# Sch1.net
KiCad netlist of a schematic drawn in Altium Designer
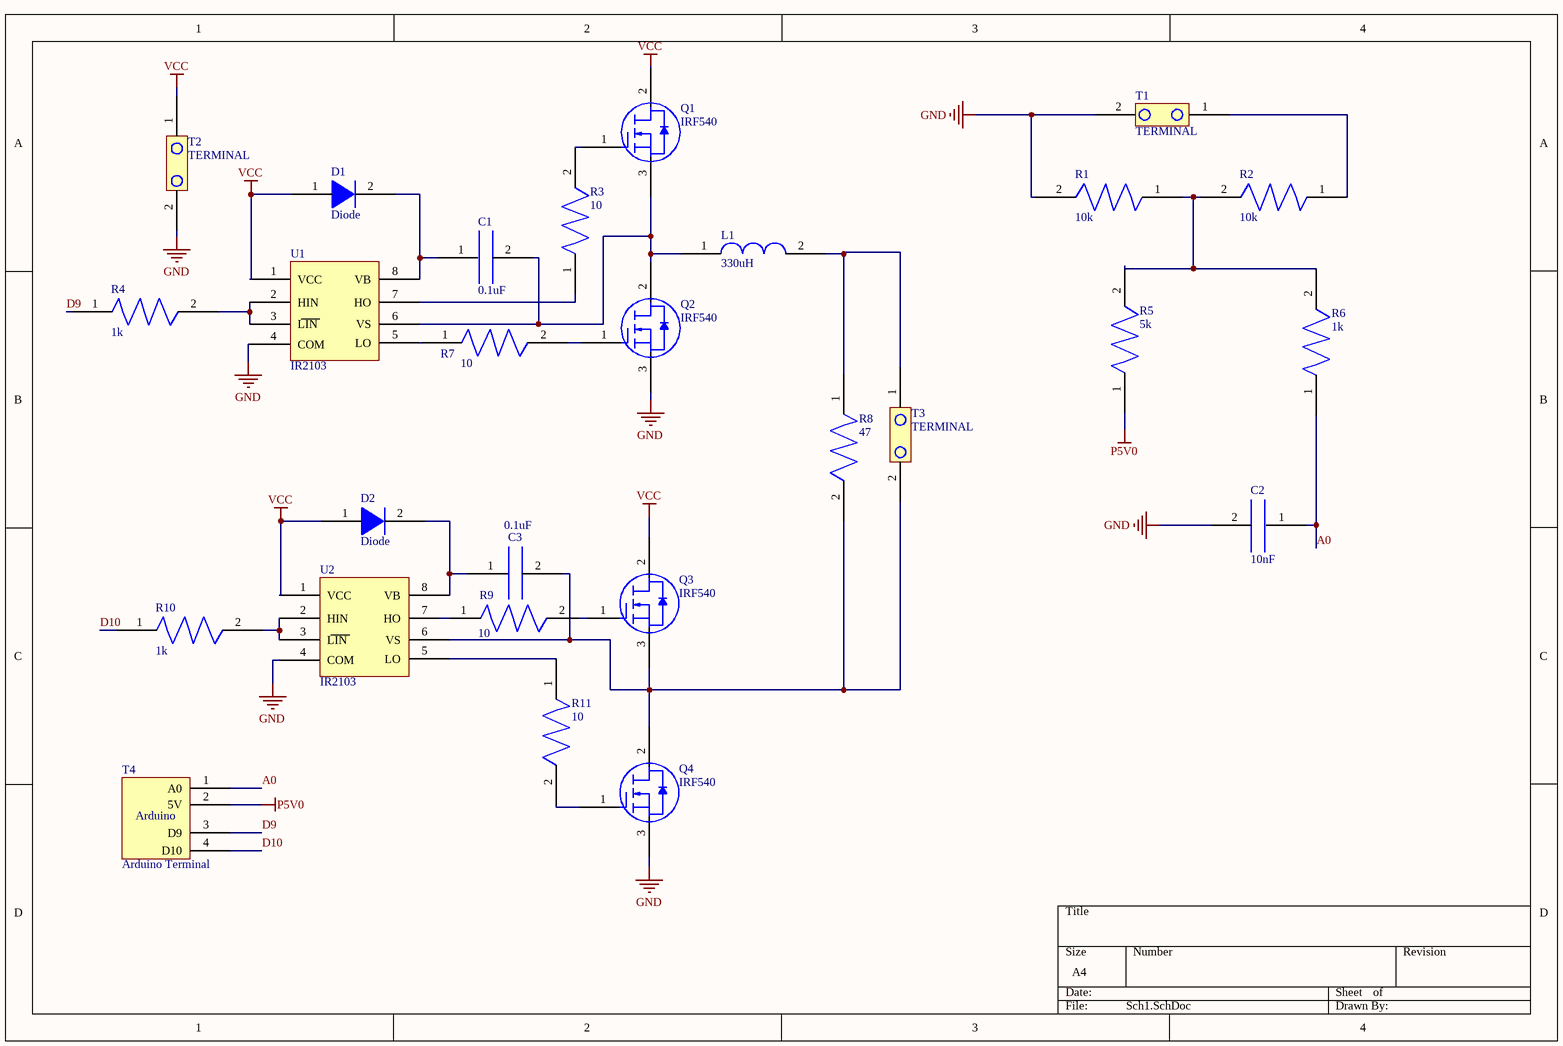
[diagram p0: Sch1.SchDoc]

(export (version "E")
  (design (tool "Eeschema 10.0.6"))
  (components
    (comp (ref "C1")
      (value "0.1uF")
      (footprint "capacitor")
      (libsource (lib "myschemlib") (part "Capacitor"))
    )
    (comp (ref "C2") (value "10nF") (footprint "capacitor") (libsource (lib "myschemlib") (part "Capacitor")))
    (comp (ref "C3")
      (value "0.1uF")
      (footprint "capacitor")
      (libsource (lib "myschemlib") (part "Capacitor"))
    )
    (comp (ref "D1") (value "Diode") (footprint "1N4148TA") (libsource (lib "myschemlib") (part "Diode")))
    (comp (ref "D2") (value "Diode") (footprint "1N4148TA") (libsource (lib "myschemlib") (part "Diode")))
    (comp (ref "L1") (value "330uH") (footprint "Inductor") (libsource (lib "myschemlib") (part "Inductor")))
    (comp (ref "Q1") (value "IRF540") (footprint "IRF540") (libsource (lib "myschemlib") (part "IRF540")))
    (comp (ref "Q2") (value "IRF540") (footprint "IRF540") (libsource (lib "myschemlib") (part "IRF540")))
    (comp (ref "Q3") (value "IRF540") (footprint "IRF540") (libsource (lib "myschemlib") (part "IRF540")))
    (comp (ref "Q4") (value "IRF540") (footprint "IRF540") (libsource (lib "myschemlib") (part "IRF540")))
    (comp (ref "R1")
      (value "10k")
      (footprint "Resistor")
      (libsource (lib "myschemlib") (part "Resistor 0805"))
    )
    (comp (ref "R2")
      (value "10k")
      (footprint "Resistor")
      (libsource (lib "myschemlib") (part "Resistor 0805"))
    )
    (comp (ref "R3")
      (value "10")
      (footprint "Resistor")
      (libsource (lib "myschemlib") (part "Resistor 0805"))
    )
    (comp (ref "R4")
      (value "1k")
      (footprint "Resistor")
      (libsource (lib "myschemlib") (part "Resistor 0805"))
    )
    (comp (ref "R5")
      (value "5k")
      (footprint "Resistor")
      (libsource (lib "myschemlib") (part "Resistor 0805"))
    )
    (comp (ref "R6")
      (value "1k")
      (footprint "Resistor")
      (libsource (lib "myschemlib") (part "Resistor 0805"))
    )
    (comp (ref "R7")
      (value "10")
      (footprint "Resistor")
      (libsource (lib "myschemlib") (part "Resistor 0805"))
    )
    (comp (ref "R8")
      (value "47")
      (footprint "Resistor")
      (libsource (lib "myschemlib") (part "Resistor 0805"))
    )
    (comp (ref "R9")
      (value "10")
      (footprint "Resistor")
      (libsource (lib "myschemlib") (part "Resistor 0805"))
    )
    (comp (ref "R10")
      (value "1k")
      (footprint "Resistor")
      (libsource (lib "myschemlib") (part "Resistor 0805"))
    )
    (comp (ref "R11")
      (value "10")
      (footprint "Resistor")
      (libsource (lib "myschemlib") (part "Resistor 0805"))
    )
    (comp (ref "T1")
      (value "TERMINAL")
      (footprint "SOURCE TERMINAL")
      (libsource (lib "") (part "TERMINAL_1"))
    )
    (comp (ref "T2")
      (value "TERMINAL")
      (footprint "SOURCE TERMINAL")
      (libsource (lib "myschemlib") (part "TERMINAL"))
    )
    (comp (ref "T3")
      (value "TERMINAL")
      (footprint "SOURCE TERMINAL")
      (libsource (lib "myschemlib") (part "TERMINAL"))
    )
    (comp (ref "T4")
      (value "Arduino Terminal")
      (footprint "ARDUINO TERMINAL")
      (libsource (lib "myschemlib") (part "Arduino Terminal"))
    )
    (comp (ref "U1") (value "IR2103") (footprint "IR2103") (libsource (lib "myschemlib") (part "IR2103")))
    (comp (ref "U2") (value "IR2103") (footprint "IR2103") (libsource (lib "myschemlib") (part "IR2103")))
  )
  (nets
    (net (code "1") (name "/A0") (class "Default")
      (node (ref "C2") (pin "1") (pinfunction "1_1") (pintype "passive"))
      (node (ref "R6") (pin "1") (pinfunction "1_1") (pintype "passive"))
      (node (ref "T4") (pin "1") (pinfunction "A0_1") (pintype "passive"))
    )
    (net (code "2") (name "/D9") (class "Default")
      (node (ref "R4") (pin "1") (pinfunction "1_1") (pintype "passive"))
      (node (ref "T4") (pin "3") (pinfunction "D9_3") (pintype "passive"))
    )
    (net (code "3") (name "/D10") (class "Default")
      (node (ref "R10") (pin "1") (pinfunction "1_1") (pintype "passive"))
      (node (ref "T4") (pin "4") (pinfunction "D10_4") (pintype "passive"))
    )
    (net (code "4") (name "GND") (class "Default")
      (node (ref "C2") (pin "2") (pinfunction "2_2") (pintype "passive"))
      (node (ref "Q2") (pin "3") (pinfunction "S_3") (pintype "passive"))
      (node (ref "Q4") (pin "3") (pinfunction "S_3") (pintype "passive"))
      (node (ref "R1") (pin "2") (pinfunction "2_2") (pintype "passive"))
      (node (ref "T1") (pin "2") (pinfunction "2_2") (pintype "passive"))
      (node (ref "T2") (pin "2") (pinfunction "2_2") (pintype "passive"))
      (node (ref "U1") (pin "4") (pinfunction "COM_4") (pintype "passive"))
      (node (ref "U2") (pin "4") (pinfunction "COM_4") (pintype "passive"))
    )
    (net (code "5") (name "Net-(L1-Pad2)") (class "Default")
      (node (ref "L1") (pin "2") (pinfunction "2_2") (pintype "passive"))
      (node (ref "R8") (pin "1") (pinfunction "1_1") (pintype "passive"))
      (node (ref "T3") (pin "1") (pinfunction "1_1") (pintype "passive"))
    )
    (net (code "6") (name "Net-(Q1-G)") (class "Default")
      (node (ref "Q1") (pin "1") (pinfunction "G_1") (pintype "passive"))
      (node (ref "R3") (pin "2") (pinfunction "2_2") (pintype "passive"))
    )
    (net (code "7") (name "Net-(Q1-S)") (class "Default")
      (node (ref "C1") (pin "2") (pinfunction "2_2") (pintype "passive"))
      (node (ref "L1") (pin "1") (pinfunction "1_1") (pintype "passive"))
      (node (ref "Q1") (pin "3") (pinfunction "S_3") (pintype "passive"))
      (node (ref "Q2") (pin "2") (pinfunction "D_2") (pintype "passive"))
      (node (ref "U1") (pin "6") (pinfunction "VS_6") (pintype "passive"))
    )
    (net (code "8") (name "Net-(Q2-G)") (class "Default")
      (node (ref "Q2") (pin "1") (pinfunction "G_1") (pintype "passive"))
      (node (ref "R7") (pin "2") (pinfunction "2_2") (pintype "passive"))
    )
    (net (code "9") (name "Net-(Q3-G)") (class "Default")
      (node (ref "Q3") (pin "1") (pinfunction "G_1") (pintype "passive"))
      (node (ref "R9") (pin "2") (pinfunction "2_2") (pintype "passive"))
    )
    (net (code "10") (name "Net-(Q3-S)") (class "Default")
      (node (ref "C3") (pin "2") (pinfunction "2_2") (pintype "passive"))
      (node (ref "Q3") (pin "3") (pinfunction "S_3") (pintype "passive"))
      (node (ref "Q4") (pin "2") (pinfunction "D_2") (pintype "passive"))
      (node (ref "R8") (pin "2") (pinfunction "2_2") (pintype "passive"))
      (node (ref "T3") (pin "2") (pinfunction "2_2") (pintype "passive"))
      (node (ref "U2") (pin "6") (pinfunction "VS_6") (pintype "passive"))
    )
    (net (code "11") (name "Net-(Q4-G)") (class "Default")
      (node (ref "Q4") (pin "1") (pinfunction "G_1") (pintype "passive"))
      (node (ref "R11") (pin "2") (pinfunction "2_2") (pintype "passive"))
    )
    (net (code "12") (name "Net-(R1-Pad1)") (class "Default")
      (node (ref "R1") (pin "1") (pinfunction "1_1") (pintype "passive"))
      (node (ref "R2") (pin "2") (pinfunction "2_2") (pintype "passive"))
      (node (ref "R5") (pin "2") (pinfunction "2_2") (pintype "passive"))
      (node (ref "R6") (pin "2") (pinfunction "2_2") (pintype "passive"))
    )
    (net (code "13") (name "Net-(R2-Pad1)") (class "Default")
      (node (ref "R2") (pin "1") (pinfunction "1_1") (pintype "passive"))
      (node (ref "T1") (pin "1") (pinfunction "1_1") (pintype "passive"))
    )
    (net (code "14") (name "Net-(U1-HIN)") (class "Default")
      (node (ref "R4") (pin "2") (pinfunction "2_2") (pintype "passive"))
      (node (ref "U1") (pin "2") (pinfunction "HIN_2") (pintype "passive"))
      (node (ref "U1") (pin "3") (pinfunction "LIN_3") (pintype "passive"))
    )
    (net (code "15") (name "Net-(U1-HO)") (class "Default")
      (node (ref "R3") (pin "1") (pinfunction "1_1") (pintype "passive"))
      (node (ref "U1") (pin "7") (pinfunction "HO_7") (pintype "passive"))
    )
    (net (code "16") (name "Net-(U1-LO)") (class "Default")
      (node (ref "R7") (pin "1") (pinfunction "1_1") (pintype "passive"))
      (node (ref "U1") (pin "5") (pinfunction "LO_5") (pintype "passive"))
    )
    (net (code "17") (name "Net-(U1-VB)") (class "Default")
      (node (ref "C1") (pin "1") (pinfunction "1_1") (pintype "passive"))
      (node (ref "D1") (pin "2") (pinfunction "2_2") (pintype "passive"))
      (node (ref "U1") (pin "8") (pinfunction "VB_8") (pintype "passive"))
    )
    (net (code "18") (name "Net-(U2-HIN)") (class "Default")
      (node (ref "R10") (pin "2") (pinfunction "2_2") (pintype "passive"))
      (node (ref "U2") (pin "2") (pinfunction "HIN_2") (pintype "passive"))
      (node (ref "U2") (pin "3") (pinfunction "LIN_3") (pintype "passive"))
    )
    (net (code "19") (name "Net-(U2-HO)") (class "Default")
      (node (ref "R9") (pin "1") (pinfunction "1_1") (pintype "passive"))
      (node (ref "U2") (pin "7") (pinfunction "HO_7") (pintype "passive"))
    )
    (net (code "20") (name "Net-(U2-LO)") (class "Default")
      (node (ref "R11") (pin "1") (pinfunction "1_1") (pintype "passive"))
      (node (ref "U2") (pin "5") (pinfunction "LO_5") (pintype "passive"))
    )
    (net (code "21") (name "Net-(U2-VB)") (class "Default")
      (node (ref "C3") (pin "1") (pinfunction "1_1") (pintype "passive"))
      (node (ref "D2") (pin "2") (pinfunction "2_2") (pintype "passive"))
      (node (ref "U2") (pin "8") (pinfunction "VB_8") (pintype "passive"))
    )
    (net (code "22") (name "P5V0") (class "Default")
      (node (ref "R5") (pin "1") (pinfunction "1_1") (pintype "passive"))
      (node (ref "T4") (pin "2") (pinfunction "5V_2") (pintype "passive"))
    )
    (net (code "23") (name "VCC") (class "Default")
      (node (ref "D1") (pin "1") (pinfunction "1_1") (pintype "passive"))
      (node (ref "D2") (pin "1") (pinfunction "1_1") (pintype "passive"))
      (node (ref "Q1") (pin "2") (pinfunction "D_2") (pintype "passive"))
      (node (ref "Q3") (pin "2") (pinfunction "D_2") (pintype "passive"))
      (node (ref "T2") (pin "1") (pinfunction "1_1") (pintype "passive"))
      (node (ref "U1") (pin "1") (pinfunction "VCC_1") (pintype "passive"))
      (node (ref "U2") (pin "1") (pinfunction "VCC_1") (pintype "passive"))
    )
  )
)
